# LocoNet_pca9685.net
KiCad netlist of a schematic drawn in EAGLE
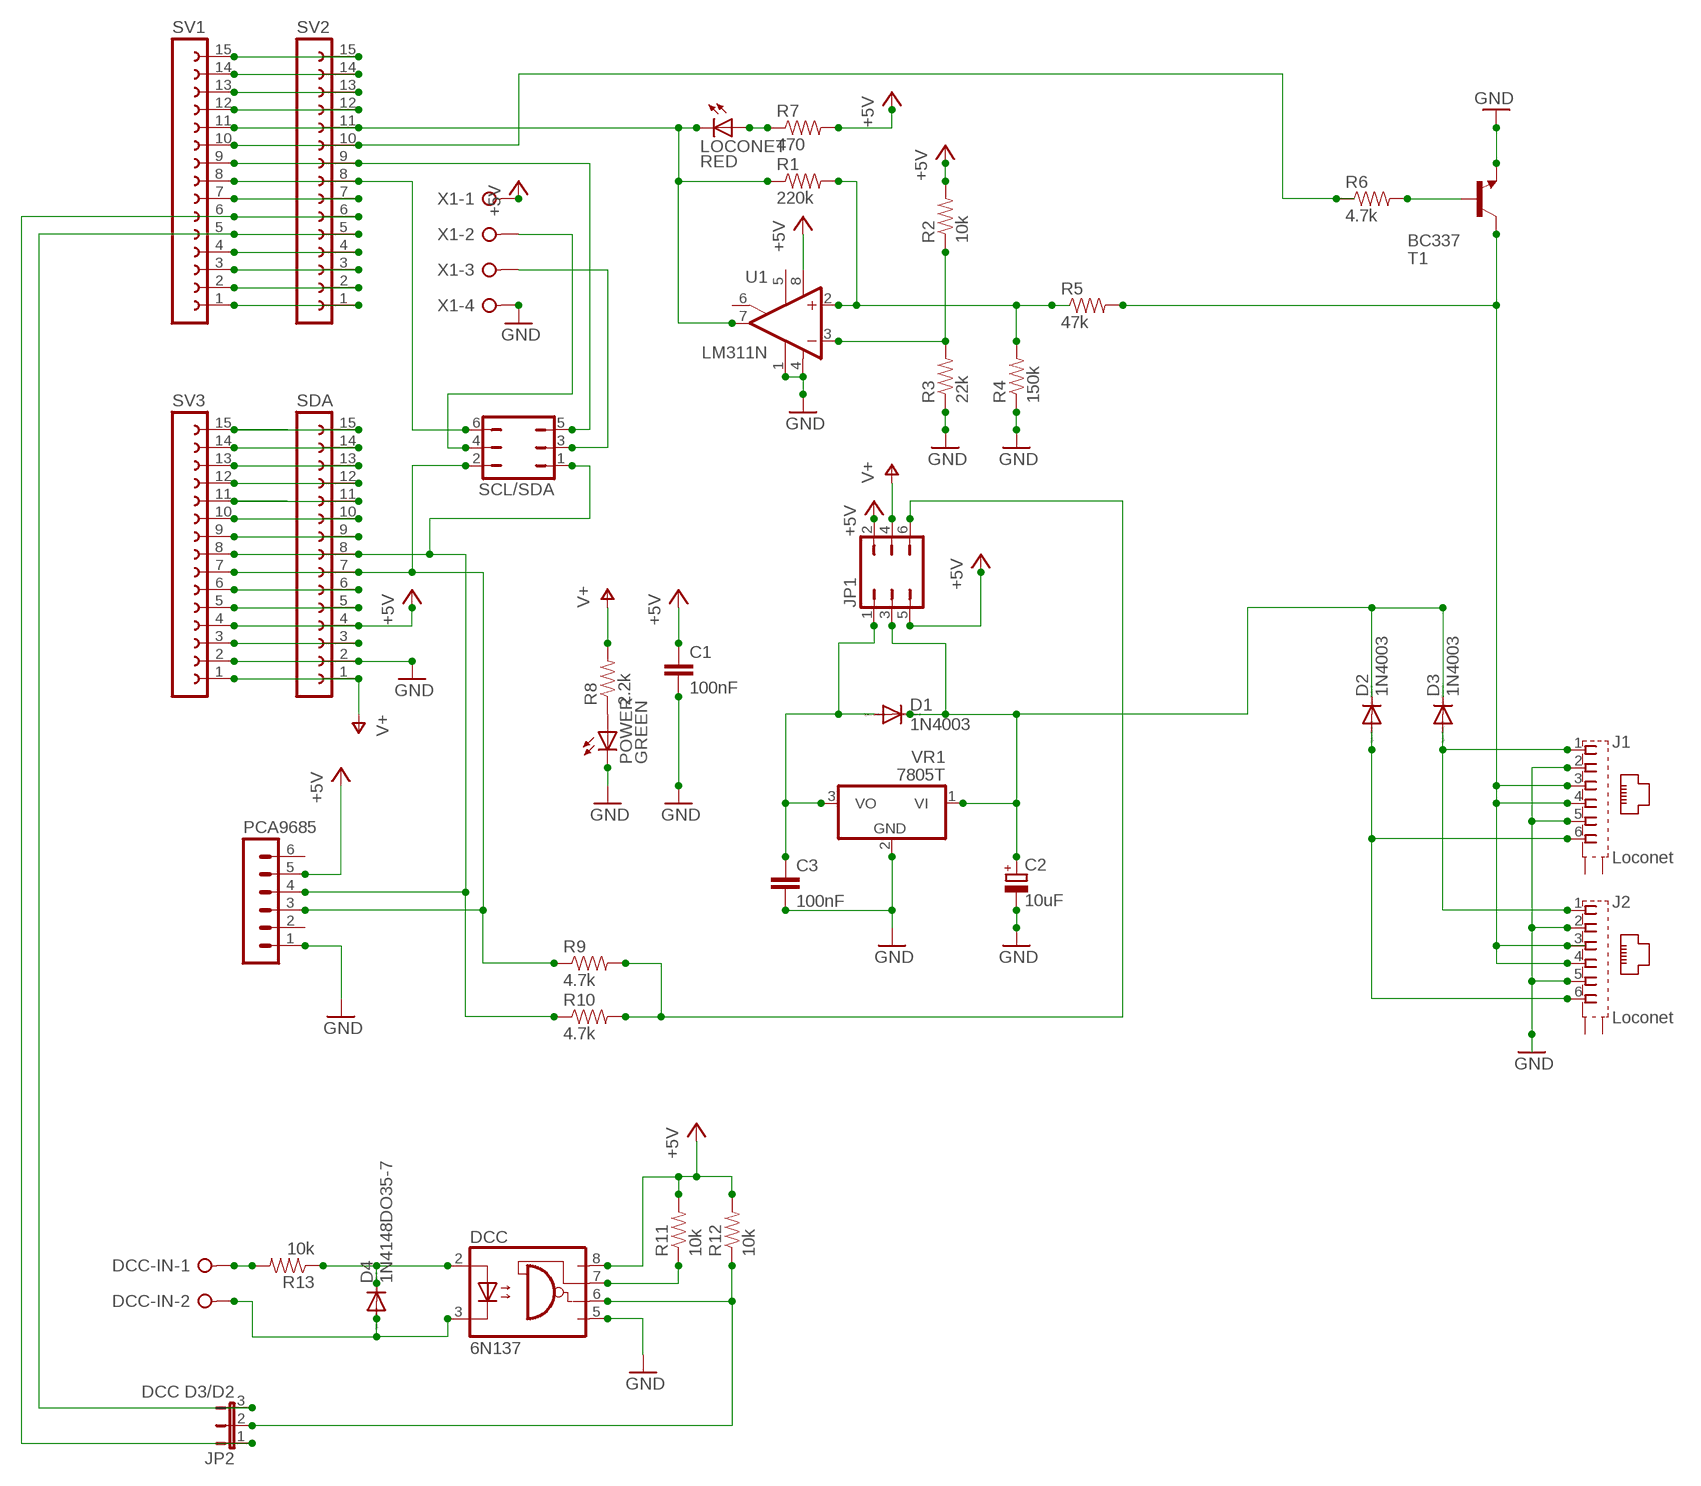
[diagram p0: schematic, sheet 1]

(export (version "E")
  (design (tool "Eeschema 10.0.6"))
  (components
    (comp (ref "C1")
      (value "100nF")
      (footprint "eagle-import:C025_050-025X075")
      (libsource (lib "eagle-import") (part "C-EU025_050-025X075"))
    )
    (comp (ref "C2")
      (value "10uF")
      (footprint "eagle-import:E2,5-6")
      (libsource (lib "eagle-import") (part "CPOL-EUE2.5-6"))
    )
    (comp (ref "C3")
      (value "100nF")
      (footprint "eagle-import:C025_050-025X075")
      (libsource (lib "eagle-import") (part "C-EU025_050-025X075"))
    )
    (comp (ref "D1")
      (value "1N4003")
      (footprint "eagle-import:DO41-10")
      (libsource (lib "eagle-import") (part "1N4004"))
    )
    (comp (ref "D2")
      (value "1N4003")
      (footprint "eagle-import:DO41-10")
      (libsource (lib "eagle-import") (part "1N4004"))
    )
    (comp (ref "D3")
      (value "1N4003")
      (footprint "eagle-import:DO41-10")
      (libsource (lib "eagle-import") (part "1N4004"))
    )
    (comp (ref "D4")
      (value "1N4148DO35-7")
      (footprint "eagle-import:DO35-7")
      (libsource (lib "eagle-import") (part "1N4148DO35-7"))
    )
    (comp (ref "DCC")
      (value "6N137")
      (footprint "eagle-import:DIL08")
      (libsource (lib "eagle-import") (part "6N137"))
    )
    (comp (ref "DCC-IN")
      (value "W237-02P")
      (footprint "eagle-import:W237-132")
      (libsource (lib "eagle-import") (part "W237-02P"))
    )
    (comp (ref "J1")
      (value "Loconet")
      (footprint "eagle-import:555140-1")
      (libsource (lib "eagle-import") (part "555140-1"))
    )
    (comp (ref "J2")
      (value "Loconet")
      (footprint "eagle-import:555140-1")
      (libsource (lib "eagle-import") (part "555140-1"))
    )
    (comp (ref "JP1")
      (value "JP3Q")
      (footprint "eagle-import:JP3Q")
      (libsource (lib "eagle-import") (part "JP3Q"))
    )
    (comp (ref "JP2")
      (value "DCC D3/D2")
      (footprint "eagle-import:JP2")
      (libsource (lib "eagle-import") (part "JP2E"))
    )
    (comp (ref "LOCONET")
      (value "RED")
      (footprint "eagle-import:LED3MM")
      (libsource (lib "eagle-import") (part "LED3MM"))
    )
    (comp (ref "PCA9685")
      (value "MA06-1")
      (footprint "eagle-import:MA06-1")
      (libsource (lib "eagle-import") (part "MA06-1"))
    )
    (comp (ref "POWER")
      (value "GREEN")
      (footprint "eagle-import:LED3MM")
      (libsource (lib "eagle-import") (part "LED3MM"))
    )
    (comp (ref "R1")
      (value "220k")
      (footprint "eagle-import:AXIAL-0.3")
      (libsource (lib "eagle-import") (part "RESISTORAXIAL-0.3"))
    )
    (comp (ref "R2")
      (value "10k")
      (footprint "eagle-import:AXIAL-0.3")
      (libsource (lib "eagle-import") (part "RESISTORAXIAL-0.3"))
    )
    (comp (ref "R3")
      (value "22k")
      (footprint "eagle-import:AXIAL-0.3")
      (libsource (lib "eagle-import") (part "RESISTORAXIAL-0.3"))
    )
    (comp (ref "R4")
      (value "150k")
      (footprint "eagle-import:AXIAL-0.3")
      (libsource (lib "eagle-import") (part "RESISTORAXIAL-0.3"))
    )
    (comp (ref "R5")
      (value "47k")
      (footprint "eagle-import:AXIAL-0.3")
      (libsource (lib "eagle-import") (part "RESISTORAXIAL-0.3"))
    )
    (comp (ref "R6")
      (value "4.7k")
      (footprint "eagle-import:AXIAL-0.3")
      (libsource (lib "eagle-import") (part "RESISTORAXIAL-0.3"))
    )
    (comp (ref "R7")
      (value "470")
      (footprint "eagle-import:AXIAL-0.3")
      (libsource (lib "eagle-import") (part "RESISTORAXIAL-0.3"))
    )
    (comp (ref "R8")
      (value "2.2k")
      (footprint "eagle-import:AXIAL-0.3")
      (libsource (lib "eagle-import") (part "RESISTORAXIAL-0.3"))
    )
    (comp (ref "R9")
      (value "4.7k")
      (footprint "eagle-import:AXIAL-0.3")
      (libsource (lib "eagle-import") (part "RESISTORAXIAL-0.3"))
    )
    (comp (ref "R10")
      (value "4.7k")
      (footprint "eagle-import:AXIAL-0.3")
      (libsource (lib "eagle-import") (part "RESISTORAXIAL-0.3"))
    )
    (comp (ref "R11")
      (value "10k")
      (footprint "eagle-import:AXIAL-0.3")
      (libsource (lib "eagle-import") (part "RESISTORAXIAL-0.3"))
    )
    (comp (ref "R12")
      (value "10k")
      (footprint "eagle-import:AXIAL-0.3")
      (libsource (lib "eagle-import") (part "RESISTORAXIAL-0.3"))
    )
    (comp (ref "R13")
      (value "10k")
      (footprint "eagle-import:AXIAL-0.3")
      (libsource (lib "eagle-import") (part "RESISTORAXIAL-0.3"))
    )
    (comp (ref "SCL/SDA")
      (value "JP3Q")
      (footprint "eagle-import:JP3Q")
      (libsource (lib "eagle-import") (part "JP3Q"))
    )
    (comp (ref "SDA")
      (value "FE15-1NOTEXT")
      (footprint "eagle-import:FE15")
      (libsource (lib "eagle-import") (part "FE15-1NOTEXT"))
    )
    (comp (ref "SV1")
      (value "FE15-1NOTEXT")
      (footprint "eagle-import:FE15")
      (libsource (lib "eagle-import") (part "FE15-1NOTEXT"))
    )
    (comp (ref "SV2")
      (value "FE15-1NOTEXT")
      (footprint "eagle-import:FE15")
      (libsource (lib "eagle-import") (part "FE15-1NOTEXT"))
    )
    (comp (ref "SV3")
      (value "FE15-1NOTEXT")
      (footprint "eagle-import:FE15")
      (libsource (lib "eagle-import") (part "FE15-1NOTEXT"))
    )
    (comp (ref "T1")
      (value "BC337")
      (footprint "eagle-import:TO92")
      (libsource (lib "eagle-import") (part "BC337"))
    )
    (comp (ref "U1")
      (value "LM311N")
      (footprint "eagle-import:DIL08")
      (libsource (lib "eagle-import") (part "LM311N"))
    )
    (comp (ref "VR1")
      (value "7805T")
      (footprint "eagle-import:TO220H")
      (libsource (lib "eagle-import") (part "78T05"))
    )
    (comp (ref "X1")
      (value "W237-04P")
      (footprint "eagle-import:W237-4P")
      (libsource (lib "eagle-import") (part "W237-04P"))
    )
  )
  (nets
    (net (code "1") (name "+5V") (class "Default")
      (node (ref "C1") (pin "1") (pinfunction "1_1") (pintype "passive"))
      (node (ref "DCC") (pin "8") (pinfunction "VCC_8") (pintype "passive"))
      (node (ref "JP1") (pin "2") (pinfunction "2_2") (pintype "passive"))
      (node (ref "JP1") (pin "5") (pinfunction "5_5") (pintype "passive"))
      (node (ref "PCA9685") (pin "5") (pinfunction "5_5") (pintype "passive"))
      (node (ref "R11") (pin "P$2") (pinfunction "2_P$2") (pintype "passive"))
      (node (ref "R12") (pin "P$2") (pinfunction "2_P$2") (pintype "passive"))
      (node (ref "R2") (pin "P$2") (pinfunction "2_P$2") (pintype "passive"))
      (node (ref "R7") (pin "P$2") (pinfunction "2_P$2") (pintype "passive"))
      (node (ref "SDA") (pin "4") (pinfunction "4_4") (pintype "passive"))
      (node (ref "SV3") (pin "4") (pinfunction "4_4") (pintype "passive"))
      (node (ref "U1") (pin "8") (pinfunction "V+_8") (pintype "power_in"))
      (node (ref "X1") (pin "1") (pinfunction "KL_1") (pintype "passive"))
    )
    (net (code "2") (name "GND") (class "Default")
      (node (ref "C1") (pin "2") (pinfunction "2_2") (pintype "passive"))
      (node (ref "C2") (pin "-") (pinfunction "-_-") (pintype "passive"))
      (node (ref "C3") (pin "2") (pinfunction "2_2") (pintype "passive"))
      (node (ref "DCC") (pin "5") (pinfunction "GND_5") (pintype "passive"))
      (node (ref "J1") (pin "2") (pinfunction "2_2") (pintype "passive"))
      (node (ref "J1") (pin "5") (pinfunction "5_5") (pintype "passive"))
      (node (ref "J2") (pin "2") (pinfunction "2_2") (pintype "passive"))
      (node (ref "J2") (pin "5") (pinfunction "5_5") (pintype "passive"))
      (node (ref "PCA9685") (pin "1") (pinfunction "1_1") (pintype "passive"))
      (node (ref "POWER") (pin "K") (pinfunction "C_K") (pintype "passive"))
      (node (ref "R3") (pin "P$1") (pinfunction "1_P$1") (pintype "passive"))
      (node (ref "R4") (pin "P$1") (pinfunction "1_P$1") (pintype "passive"))
      (node (ref "SDA") (pin "2") (pinfunction "2_2") (pintype "passive"))
      (node (ref "SV3") (pin "2") (pinfunction "2_2") (pintype "passive"))
      (node (ref "T1") (pin "1") (pinfunction "E_1") (pintype "passive"))
      (node (ref "U1") (pin "1") (pinfunction "GND_1") (pintype "passive"))
      (node (ref "U1") (pin "4") (pinfunction "V-_4") (pintype "power_in"))
      (node (ref "VR1") (pin "2") (pinfunction "GND_2") (pintype "passive"))
      (node (ref "X1") (pin "4") (pinfunction "KL_4") (pintype "passive"))
    )
    (net (code "3") (name "Net-(D2-PadA)") (class "Default")
      (node (ref "D2") (pin "A") (pinfunction "A_A") (pintype "passive"))
      (node (ref "J1") (pin "6") (pinfunction "6_6") (pintype "passive"))
      (node (ref "J2") (pin "6") (pinfunction "6_6") (pintype "passive"))
    )
    (net (code "4") (name "Net-(D3-PadA)") (class "Default")
      (node (ref "D3") (pin "A") (pinfunction "A_A") (pintype "passive"))
      (node (ref "J1") (pin "1") (pinfunction "1_1") (pintype "passive"))
      (node (ref "J2") (pin "1") (pinfunction "1_1") (pintype "passive"))
    )
    (net (code "5") (name "Net-(DCC-A)") (class "Default")
      (node (ref "D4") (pin "C") (pinfunction "C_C") (pintype "passive"))
      (node (ref "DCC") (pin "2") (pinfunction "A_2") (pintype "passive"))
      (node (ref "R13") (pin "P$1") (pinfunction "1_P$1") (pintype "passive"))
    )
    (net (code "6") (name "Net-(DCC-C)") (class "Default")
      (node (ref "D4") (pin "A") (pinfunction "A_A") (pintype "passive"))
      (node (ref "DCC") (pin "3") (pinfunction "C_3") (pintype "passive"))
      (node (ref "DCC-IN") (pin "2") (pinfunction "KL_2") (pintype "passive"))
    )
    (net (code "7") (name "Net-(DCC-INA-KL)") (class "Default")
      (node (ref "DCC-IN") (pin "1") (pinfunction "KL_1") (pintype "passive"))
      (node (ref "R13") (pin "P$2") (pinfunction "2_P$2") (pintype "passive"))
    )
    (net (code "8") (name "Net-(DCC-VE)") (class "Default")
      (node (ref "DCC") (pin "7") (pinfunction "VE_7") (pintype "passive"))
      (node (ref "R11") (pin "P$1") (pinfunction "1_P$1") (pintype "passive"))
    )
    (net (code "9") (name "Net-(DCC-VO)") (class "Default")
      (node (ref "DCC") (pin "6") (pinfunction "VO_6") (pintype "passive"))
      (node (ref "JP2") (pin "2") (pinfunction "2_2") (pintype "passive"))
      (node (ref "R12") (pin "P$1") (pinfunction "1_P$1") (pintype "passive"))
    )
    (net (code "10") (name "Net-(JP2-Pad1)") (class "Default")
      (node (ref "JP2") (pin "1") (pinfunction "1_1") (pintype "passive"))
      (node (ref "SV1") (pin "6") (pinfunction "6_6") (pintype "passive"))
      (node (ref "SV2") (pin "6") (pinfunction "6_6") (pintype "passive"))
    )
    (net (code "11") (name "Net-(JP2-Pad3)") (class "Default")
      (node (ref "JP2") (pin "3") (pinfunction "3_3") (pintype "passive"))
      (node (ref "SV1") (pin "5") (pinfunction "5_5") (pintype "passive"))
      (node (ref "SV2") (pin "5") (pinfunction "5_5") (pintype "passive"))
    )
    (net (code "12") (name "Net-(LOCONET-C)") (class "Default")
      (node (ref "LOCONET") (pin "K") (pinfunction "C_K") (pintype "passive"))
      (node (ref "R1") (pin "P$1") (pinfunction "1_P$1") (pintype "passive"))
      (node (ref "SV1") (pin "11") (pinfunction "11_11") (pintype "passive"))
      (node (ref "SV2") (pin "11") (pinfunction "11_11") (pintype "passive"))
      (node (ref "U1") (pin "7") (pinfunction "OUT_7") (pintype "output"))
    )
    (net (code "13") (name "Net-(R1-2)") (class "Default")
      (node (ref "R1") (pin "P$2") (pinfunction "2_P$2") (pintype "passive"))
      (node (ref "R4") (pin "P$2") (pinfunction "2_P$2") (pintype "passive"))
      (node (ref "R5") (pin "P$1") (pinfunction "1_P$1") (pintype "passive"))
      (node (ref "U1") (pin "2") (pinfunction "+IN_2") (pintype "input"))
    )
    (net (code "14") (name "Net-(R2-1)") (class "Default")
      (node (ref "R2") (pin "P$1") (pinfunction "1_P$1") (pintype "passive"))
      (node (ref "R3") (pin "P$2") (pinfunction "2_P$2") (pintype "passive"))
      (node (ref "U1") (pin "3") (pinfunction "-IN_3") (pintype "input"))
    )
    (net (code "15") (name "Net-(R5-2)") (class "Default")
      (node (ref "J1") (pin "3") (pinfunction "3_3") (pintype "passive"))
      (node (ref "J1") (pin "4") (pinfunction "4_4") (pintype "passive"))
      (node (ref "J2") (pin "3") (pinfunction "3_3") (pintype "passive"))
      (node (ref "J2") (pin "4") (pinfunction "4_4") (pintype "passive"))
      (node (ref "R5") (pin "P$2") (pinfunction "2_P$2") (pintype "passive"))
      (node (ref "T1") (pin "3") (pinfunction "C_3") (pintype "passive"))
    )
    (net (code "16") (name "Net-(R6-1)") (class "Default")
      (node (ref "R6") (pin "P$1") (pinfunction "1_P$1") (pintype "passive"))
      (node (ref "SV1") (pin "10") (pinfunction "10_10") (pintype "passive"))
      (node (ref "SV2") (pin "10") (pinfunction "10_10") (pintype "passive"))
    )
    (net (code "17") (name "Net-(R6-2)") (class "Default")
      (node (ref "R6") (pin "P$2") (pinfunction "2_P$2") (pintype "passive"))
      (node (ref "T1") (pin "2") (pinfunction "B_2") (pintype "passive"))
    )
    (net (code "18") (name "Net-(R7-1)") (class "Default")
      (node (ref "LOCONET") (pin "A") (pinfunction "A_A") (pintype "passive"))
      (node (ref "R7") (pin "P$1") (pinfunction "1_P$1") (pintype "passive"))
    )
    (net (code "19") (name "Net-(R8-1)") (class "Default")
      (node (ref "POWER") (pin "A") (pinfunction "A_A") (pintype "passive"))
      (node (ref "R8") (pin "P$1") (pinfunction "1_P$1") (pintype "passive"))
    )
    (net (code "20") (name "Net-(R9-1)") (class "Default")
      (node (ref "PCA9685") (pin "3") (pinfunction "3_3") (pintype "passive"))
      (node (ref "R9") (pin "P$1") (pinfunction "1_P$1") (pintype "passive"))
      (node (ref "SCL/SDA") (pin "2") (pinfunction "2_2") (pintype "passive"))
      (node (ref "SDA") (pin "7") (pinfunction "7_7") (pintype "passive"))
      (node (ref "SV3") (pin "7") (pinfunction "7_7") (pintype "passive"))
    )
    (net (code "21") (name "Net-(R10-1)") (class "Default")
      (node (ref "PCA9685") (pin "4") (pinfunction "4_4") (pintype "passive"))
      (node (ref "R10") (pin "P$1") (pinfunction "1_P$1") (pintype "passive"))
      (node (ref "SCL/SDA") (pin "1") (pinfunction "1_1") (pintype "passive"))
      (node (ref "SDA") (pin "8") (pinfunction "8_8") (pintype "passive"))
      (node (ref "SV3") (pin "8") (pinfunction "8_8") (pintype "passive"))
    )
    (net (code "22") (name "Net-(R10-2)") (class "Default")
      (node (ref "JP1") (pin "6") (pinfunction "6_6") (pintype "passive"))
      (node (ref "R10") (pin "P$2") (pinfunction "2_P$2") (pintype "passive"))
      (node (ref "R9") (pin "P$2") (pinfunction "2_P$2") (pintype "passive"))
    )
    (net (code "23") (name "Net-(SCL/SDA-Pad5)") (class "Default")
      (node (ref "SCL/SDA") (pin "5") (pinfunction "5_5") (pintype "passive"))
      (node (ref "SV1") (pin "9") (pinfunction "9_9") (pintype "passive"))
      (node (ref "SV2") (pin "9") (pinfunction "9_9") (pintype "passive"))
    )
    (net (code "24") (name "Net-(SCL/SDA-Pad6)") (class "Default")
      (node (ref "SCL/SDA") (pin "6") (pinfunction "6_6") (pintype "passive"))
      (node (ref "SV1") (pin "8") (pinfunction "8_8") (pintype "passive"))
      (node (ref "SV2") (pin "8") (pinfunction "8_8") (pintype "passive"))
    )
    (net (code "25") (name "Net-(SDA-Pad3)") (class "Default")
      (node (ref "SDA") (pin "3") (pinfunction "3_3") (pintype "passive"))
      (node (ref "SV3") (pin "3") (pinfunction "3_3") (pintype "passive"))
    )
    (net (code "26") (name "Net-(SDA-Pad5)") (class "Default")
      (node (ref "SDA") (pin "5") (pinfunction "5_5") (pintype "passive"))
      (node (ref "SV3") (pin "5") (pinfunction "5_5") (pintype "passive"))
    )
    (net (code "27") (name "Net-(SDA-Pad6)") (class "Default")
      (node (ref "SDA") (pin "6") (pinfunction "6_6") (pintype "passive"))
      (node (ref "SV3") (pin "6") (pinfunction "6_6") (pintype "passive"))
    )
    (net (code "28") (name "Net-(SDA-Pad9)") (class "Default")
      (node (ref "SDA") (pin "9") (pinfunction "9_9") (pintype "passive"))
      (node (ref "SV3") (pin "9") (pinfunction "9_9") (pintype "passive"))
    )
    (net (code "29") (name "Net-(SDA-Pad10)") (class "Default")
      (node (ref "SDA") (pin "10") (pinfunction "10_10") (pintype "passive"))
      (node (ref "SV3") (pin "10") (pinfunction "10_10") (pintype "passive"))
    )
    (net (code "30") (name "Net-(SDA-Pad11)") (class "Default")
      (node (ref "SDA") (pin "11") (pinfunction "11_11") (pintype "passive"))
      (node (ref "SV3") (pin "11") (pinfunction "11_11") (pintype "passive"))
    )
    (net (code "31") (name "Net-(SDA-Pad12)") (class "Default")
      (node (ref "SDA") (pin "12") (pinfunction "12_12") (pintype "passive"))
      (node (ref "SV3") (pin "12") (pinfunction "12_12") (pintype "passive"))
    )
    (net (code "32") (name "Net-(SDA-Pad13)") (class "Default")
      (node (ref "SDA") (pin "13") (pinfunction "13_13") (pintype "passive"))
      (node (ref "SV3") (pin "13") (pinfunction "13_13") (pintype "passive"))
    )
    (net (code "33") (name "Net-(SDA-Pad14)") (class "Default")
      (node (ref "SDA") (pin "14") (pinfunction "14_14") (pintype "passive"))
      (node (ref "SV3") (pin "14") (pinfunction "14_14") (pintype "passive"))
    )
    (net (code "34") (name "Net-(SDA-Pad15)") (class "Default")
      (node (ref "SDA") (pin "15") (pinfunction "15_15") (pintype "passive"))
      (node (ref "SV3") (pin "15") (pinfunction "15_15") (pintype "passive"))
    )
    (net (code "35") (name "Net-(SV1-Pad1)") (class "Default")
      (node (ref "SV1") (pin "1") (pinfunction "1_1") (pintype "passive"))
      (node (ref "SV2") (pin "1") (pinfunction "1_1") (pintype "passive"))
    )
    (net (code "36") (name "Net-(SV1-Pad2)") (class "Default")
      (node (ref "SV1") (pin "2") (pinfunction "2_2") (pintype "passive"))
      (node (ref "SV2") (pin "2") (pinfunction "2_2") (pintype "passive"))
    )
    (net (code "37") (name "Net-(SV1-Pad3)") (class "Default")
      (node (ref "SV1") (pin "3") (pinfunction "3_3") (pintype "passive"))
      (node (ref "SV2") (pin "3") (pinfunction "3_3") (pintype "passive"))
    )
    (net (code "38") (name "Net-(SV1-Pad4)") (class "Default")
      (node (ref "SV1") (pin "4") (pinfunction "4_4") (pintype "passive"))
      (node (ref "SV2") (pin "4") (pinfunction "4_4") (pintype "passive"))
    )
    (net (code "39") (name "Net-(SV1-Pad7)") (class "Default")
      (node (ref "SV1") (pin "7") (pinfunction "7_7") (pintype "passive"))
      (node (ref "SV2") (pin "7") (pinfunction "7_7") (pintype "passive"))
    )
    (net (code "40") (name "Net-(SV1-Pad12)") (class "Default")
      (node (ref "SV1") (pin "12") (pinfunction "12_12") (pintype "passive"))
      (node (ref "SV2") (pin "12") (pinfunction "12_12") (pintype "passive"))
    )
    (net (code "41") (name "Net-(SV1-Pad13)") (class "Default")
      (node (ref "SV1") (pin "13") (pinfunction "13_13") (pintype "passive"))
      (node (ref "SV2") (pin "13") (pinfunction "13_13") (pintype "passive"))
    )
    (net (code "42") (name "Net-(SV1-Pad14)") (class "Default")
      (node (ref "SV1") (pin "14") (pinfunction "14_14") (pintype "passive"))
      (node (ref "SV2") (pin "14") (pinfunction "14_14") (pintype "passive"))
    )
    (net (code "43") (name "Net-(SV1-Pad15)") (class "Default")
      (node (ref "SV1") (pin "15") (pinfunction "15_15") (pintype "passive"))
      (node (ref "SV2") (pin "15") (pinfunction "15_15") (pintype "passive"))
    )
    (net (code "44") (name "Net-(VR1-VI)") (class "Default")
      (node (ref "C2") (pin "+") (pinfunction "+_+") (pintype "passive"))
      (node (ref "D1") (pin "C") (pinfunction "C_C") (pintype "passive"))
      (node (ref "D2") (pin "C") (pinfunction "C_C") (pintype "passive"))
      (node (ref "D3") (pin "C") (pinfunction "C_C") (pintype "passive"))
      (node (ref "JP1") (pin "3") (pinfunction "3_3") (pintype "passive"))
      (node (ref "VR1") (pin "1") (pinfunction "VI_1") (pintype "input"))
    )
    (net (code "45") (name "Net-(VR1-VO)") (class "Default")
      (node (ref "C3") (pin "1") (pinfunction "1_1") (pintype "passive"))
      (node (ref "D1") (pin "A") (pinfunction "A_A") (pintype "passive"))
      (node (ref "JP1") (pin "1") (pinfunction "1_1") (pintype "passive"))
      (node (ref "VR1") (pin "3") (pinfunction "VO_3") (pintype "passive"))
    )
    (net (code "46") (name "Net-(X1B-KL)") (class "Default")
      (node (ref "SCL/SDA") (pin "4") (pinfunction "4_4") (pintype "passive"))
      (node (ref "X1") (pin "2") (pinfunction "KL_2") (pintype "passive"))
    )
    (net (code "47") (name "Net-(X1C-KL)") (class "Default")
      (node (ref "SCL/SDA") (pin "3") (pinfunction "3_3") (pintype "passive"))
      (node (ref "X1") (pin "3") (pinfunction "KL_3") (pintype "passive"))
    )
    (net (code "48") (name "V+") (class "Default")
      (node (ref "JP1") (pin "4") (pinfunction "4_4") (pintype "passive"))
      (node (ref "R8") (pin "P$2") (pinfunction "2_P$2") (pintype "passive"))
      (node (ref "SDA") (pin "1") (pinfunction "1_1") (pintype "passive"))
      (node (ref "SV3") (pin "1") (pinfunction "1_1") (pintype "passive"))
    )
    (net (code "49") (name "unconnected-(J1-S1-PadG1)") (class "Default")
      (node (ref "J1") (pin "G1") (pinfunction "S1_G1") (pintype "passive"))
    )
    (net (code "50") (name "unconnected-(J1-S2-PadG2)") (class "Default")
      (node (ref "J1") (pin "G2") (pinfunction "S2_G2") (pintype "passive"))
    )
    (net (code "51") (name "unconnected-(J2-S1-PadG1)") (class "Default")
      (node (ref "J2") (pin "G1") (pinfunction "S1_G1") (pintype "passive"))
    )
    (net (code "52") (name "unconnected-(J2-S2-PadG2)") (class "Default")
      (node (ref "J2") (pin "G2") (pinfunction "S2_G2") (pintype "passive"))
    )
    (net (code "53") (name "unconnected-(PCA9685-Pad2)") (class "Default")
      (node (ref "PCA9685") (pin "2") (pinfunction "2_2") (pintype "passive"))
    )
    (net (code "54") (name "unconnected-(PCA9685-Pad6)") (class "Default")
      (node (ref "PCA9685") (pin "6") (pinfunction "6_6") (pintype "passive"))
    )
    (net (code "55") (name "unconnected-(U1-ON-Pad5)") (class "Default")
      (node (ref "U1") (pin "5") (pinfunction "ON_5") (pintype "passive"))
    )
    (net (code "56") (name "unconnected-(U1-ON{slash}STR-Pad6)") (class "Default")
      (node (ref "U1") (pin "6") (pinfunction "ON/STR_6") (pintype "passive"))
    )
  )
)
